# SCH_ardiuno_2024-06-28.net
KiCad netlist of a schematic drawn in EasyEDA
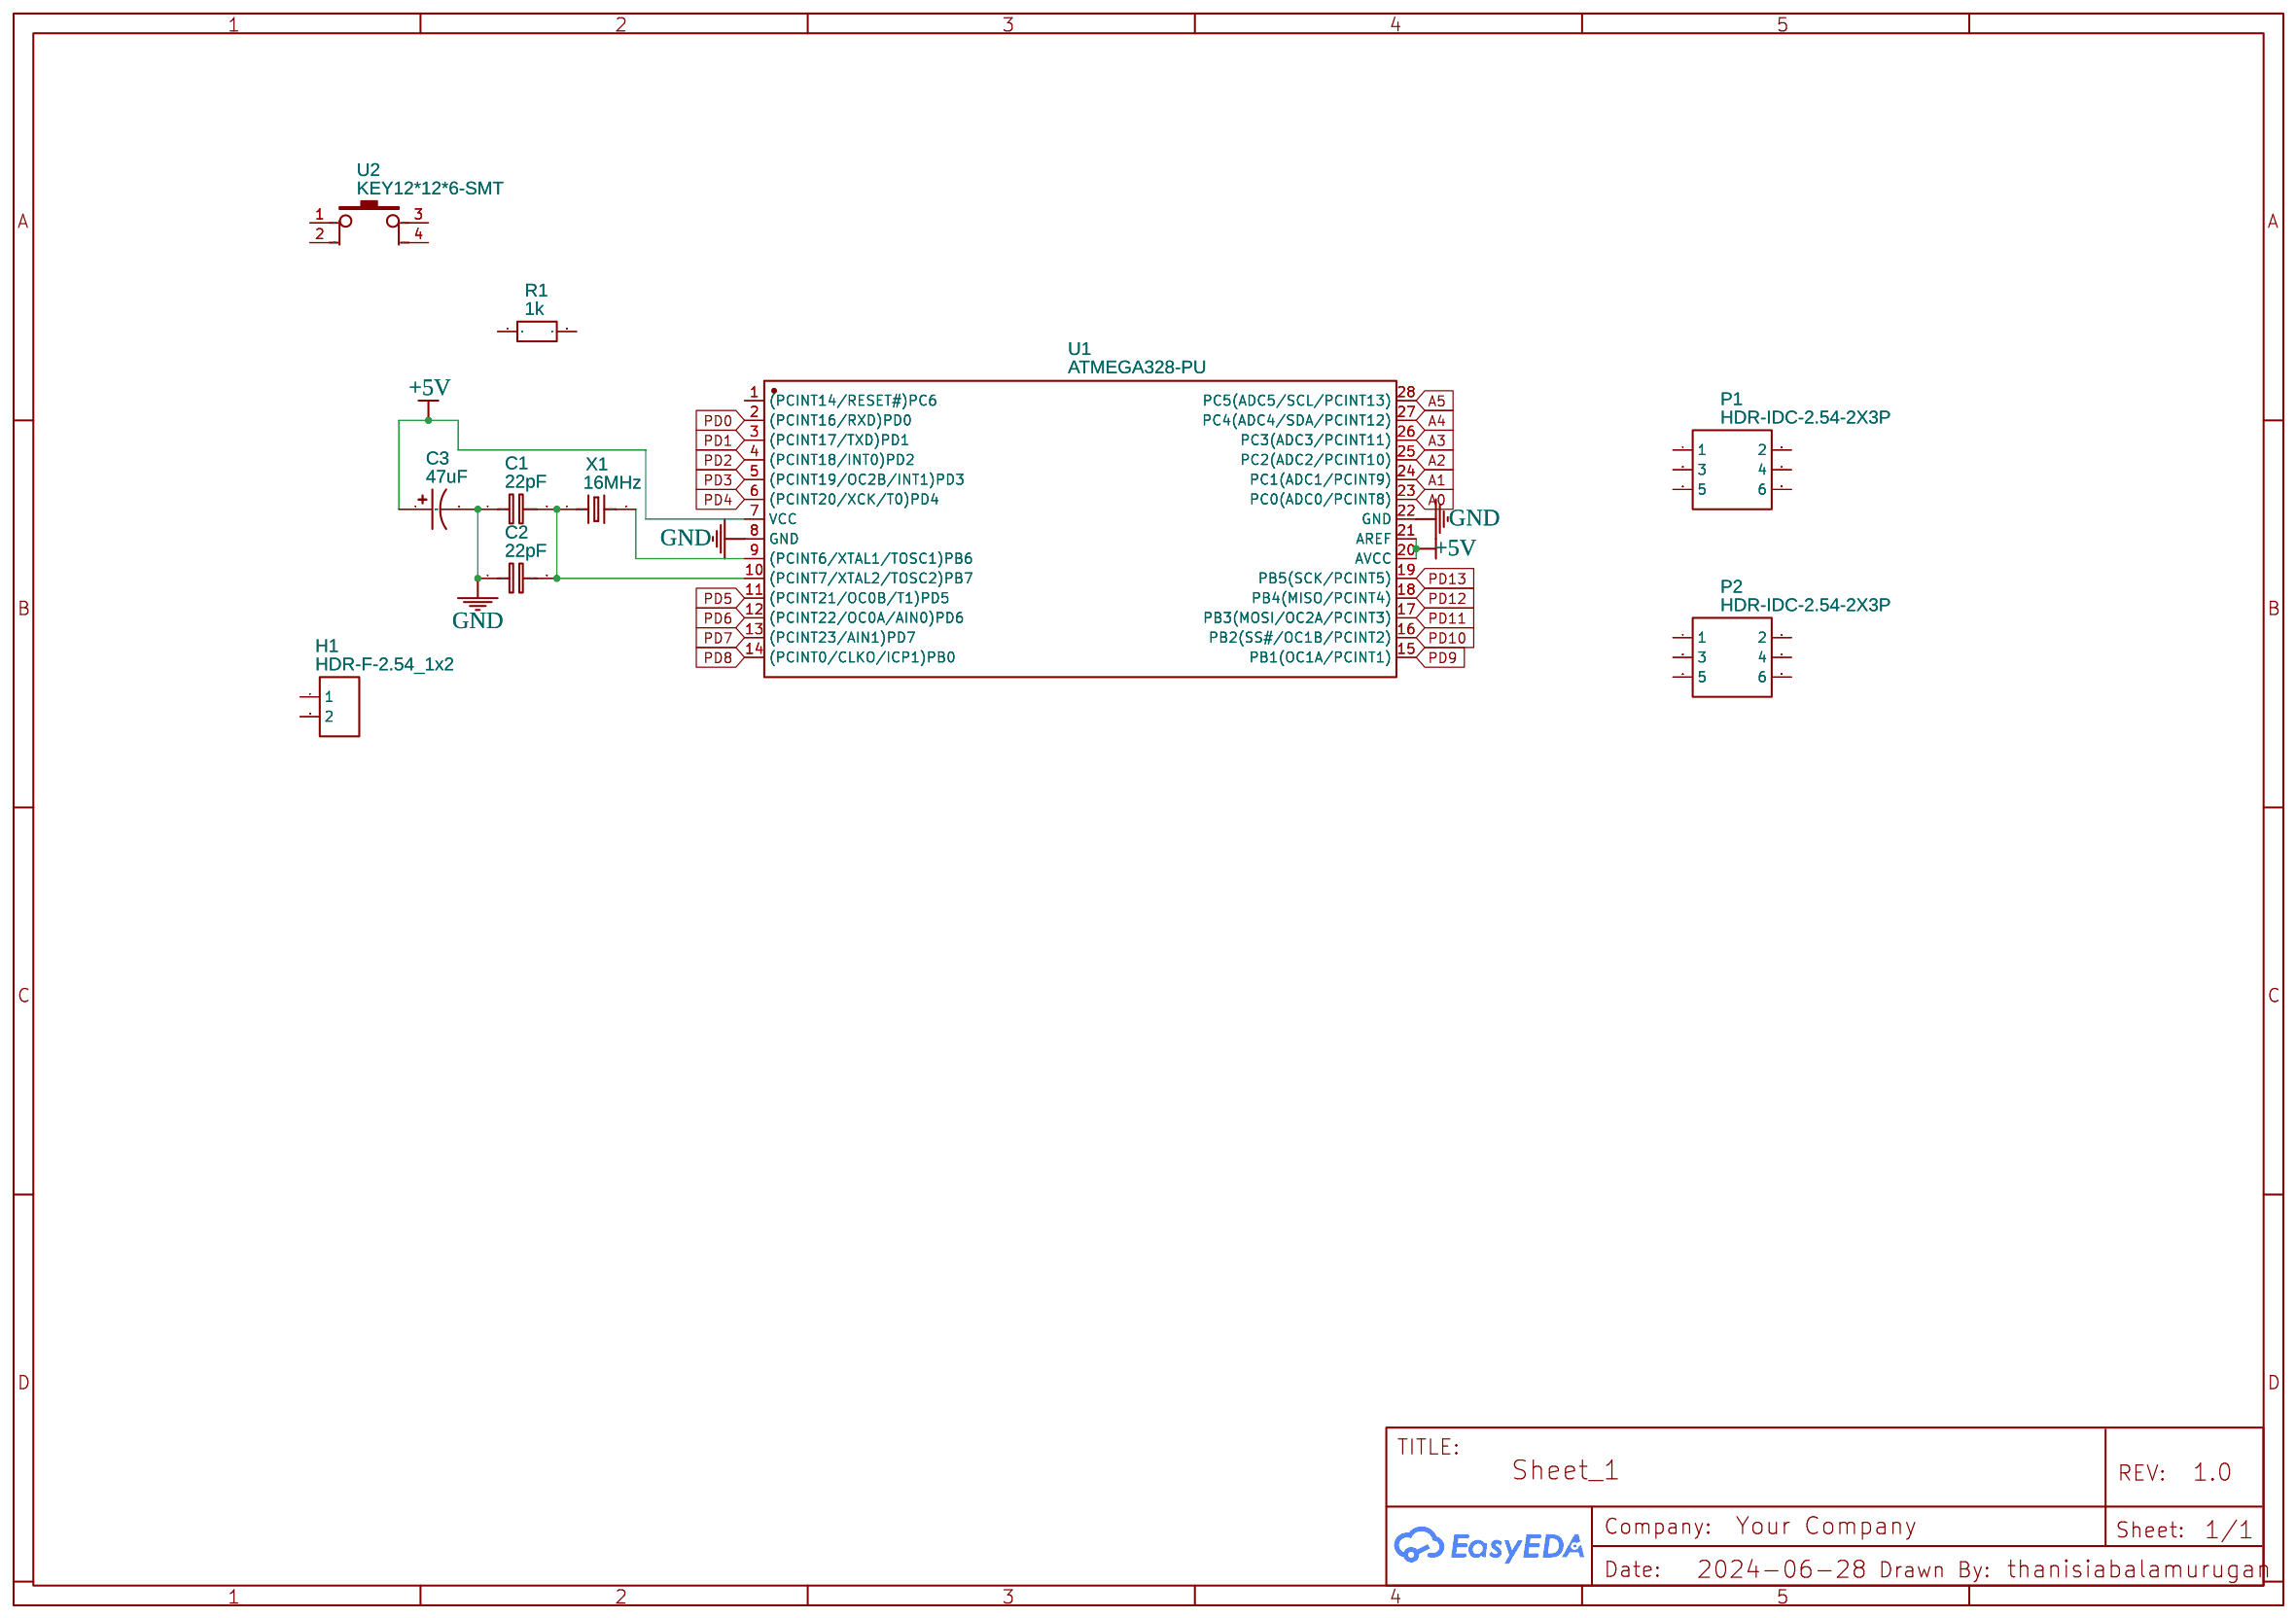
[diagram p0: schematic sheet]

(export (version "E")
  (design (tool "Eeschema 10.0.6"))
  (components
    (comp (ref "C1") (value "22pF") (libsource (lib "") (part "C_0603_EU")))
    (comp (ref "C2") (value "22pF") (libsource (lib "") (part "C_0603_EU")))
    (comp (ref "C3") (value "47uF") (libsource (lib "") (part "C_Tan_SMD_A_US")))
    (comp (ref "H1") (value "HDR-F-2.54_1x2") (libsource (lib "") (part "HDR-F-2.54_1x2")))
    (comp (ref "P1")
      (value "HDR-IDC-2.54-2X3P")
      (fields (field (name "Manufacturer Part") "2X3 2.54mm IDC Box") (field (name "Manufacturer") "BOOMELE"))
      (libsource (lib "") (part "HDR-IDC-2.54-2X3P"))
    )
    (comp (ref "P2")
      (value "HDR-IDC-2.54-2X3P")
      (fields (field (name "Manufacturer Part") "2X3 2.54mm IDC Box") (field (name "Manufacturer") "BOOMELE"))
      (libsource (lib "") (part "HDR-IDC-2.54-2X3P"))
    )
    (comp (ref "R1") (value "1k") (libsource (lib "") (part "R_0603_EU")))
    (comp (ref "U1")
      (value "ATMEGA328-PU")
      (fields (field (name "Manufacturer") "MICROCHIP(美国微芯)"))
      (libsource (lib "") (part "ATMEGA328-PU"))
    )
    (comp (ref "U2") (value "KEY12*12*6-SMT") (libsource (lib "") (part "KEY12*12*6-SMT")))
    (comp (ref "X1")
      (value "16MHz")
      (fields
        (field (name "Manufacturer Part") "XIHCELNANF-16MHZ")
        (field (name "Manufacturer") "TAITIEN(泰艺电子)")
      )
      (libsource (lib "") (part "XIHCELNANF-16MHZ"))
    )
  )
  (nets
    (net (code "1") (name "+5V") (class "Default")
      (node (ref "C3") (pin "1") (pinfunction "1_1") (pintype "unspecified"))
      (node (ref "U1") (pin "20") (pinfunction "AVCC_20") (pintype "unspecified"))
      (node (ref "U1") (pin "21") (pinfunction "AREF_21") (pintype "unspecified"))
      (node (ref "U1") (pin "7") (pinfunction "VCC_7") (pintype "unspecified"))
    )
    (net (code "2") (name "A0") (class "Default")
      (node (ref "U1") (pin "23") (pinfunction "PC0(ADC0/PCINT8)_23") (pintype "unspecified"))
    )
    (net (code "3") (name "A1") (class "Default")
      (node (ref "U1") (pin "24") (pinfunction "PC1(ADC1/PCINT9)_24") (pintype "unspecified"))
    )
    (net (code "4") (name "A2") (class "Default")
      (node (ref "U1") (pin "25") (pinfunction "PC2(ADC2/PCINT10)_25") (pintype "unspecified"))
    )
    (net (code "5") (name "A3") (class "Default")
      (node (ref "U1") (pin "26") (pinfunction "PC3(ADC3/PCINT11)_26") (pintype "unspecified"))
    )
    (net (code "6") (name "A4") (class "Default")
      (node (ref "U1") (pin "27") (pinfunction "PC4(ADC4/SDA/PCINT12)_27") (pintype "unspecified"))
    )
    (net (code "7") (name "A5") (class "Default")
      (node (ref "U1") (pin "28") (pinfunction "PC5(ADC5/SCL/PCINT13)_28") (pintype "unspecified"))
    )
    (net (code "8") (name "GND") (class "Default")
      (node (ref "C1") (pin "1") (pinfunction "1_1") (pintype "unspecified"))
      (node (ref "C2") (pin "1") (pinfunction "1_1") (pintype "unspecified"))
      (node (ref "C3") (pin "2") (pinfunction "2_2") (pintype "unspecified"))
      (node (ref "U1") (pin "22") (pinfunction "GND_22") (pintype "unspecified"))
      (node (ref "U1") (pin "8") (pinfunction "GND_8") (pintype "unspecified"))
    )
    (net (code "9") (name "Net-(U1-(PCINT6{slash}XTAL1{slash}TOSC1)PB6)") (class "Default")
      (node (ref "U1") (pin "9") (pinfunction "(PCINT6/XTAL1/TOSC1)PB6_9") (pintype "unspecified"))
      (node (ref "X1") (pin "2") (pinfunction "2_2") (pintype "unspecified"))
    )
    (net (code "10") (name "Net-(U1-(PCINT7{slash}XTAL2{slash}TOSC2)PB7)") (class "Default")
      (node (ref "C1") (pin "2") (pinfunction "2_2") (pintype "unspecified"))
      (node (ref "C2") (pin "2") (pinfunction "2_2") (pintype "unspecified"))
      (node (ref "U1") (pin "10") (pinfunction "(PCINT7/XTAL2/TOSC2)PB7_10") (pintype "unspecified"))
      (node (ref "X1") (pin "1") (pinfunction "1_1") (pintype "unspecified"))
    )
    (net (code "11") (name "PD0") (class "Default")
      (node (ref "U1") (pin "2") (pinfunction "(PCINT16/RXD)PD0_2") (pintype "unspecified"))
    )
    (net (code "12") (name "PD1") (class "Default")
      (node (ref "U1") (pin "3") (pinfunction "(PCINT17/TXD)PD1_3") (pintype "unspecified"))
    )
    (net (code "13") (name "PD2") (class "Default")
      (node (ref "U1") (pin "4") (pinfunction "(PCINT18/INT0)PD2_4") (pintype "unspecified"))
    )
    (net (code "14") (name "PD3") (class "Default")
      (node (ref "U1") (pin "5") (pinfunction "(PCINT19/OC2B/INT1)PD3_5") (pintype "unspecified"))
    )
    (net (code "15") (name "PD4") (class "Default")
      (node (ref "U1") (pin "6") (pinfunction "(PCINT20/XCK/T0)PD4_6") (pintype "unspecified"))
    )
    (net (code "16") (name "PD5") (class "Default")
      (node (ref "U1") (pin "11") (pinfunction "(PCINT21/OC0B/T1)PD5_11") (pintype "unspecified"))
    )
    (net (code "17") (name "PD6") (class "Default")
      (node (ref "U1") (pin "12") (pinfunction "(PCINT22/OC0A/AIN0)PD6_12") (pintype "unspecified"))
    )
    (net (code "18") (name "PD7") (class "Default")
      (node (ref "U1") (pin "13") (pinfunction "(PCINT23/AIN1)PD7_13") (pintype "unspecified"))
    )
    (net (code "19") (name "PD8") (class "Default")
      (node (ref "U1") (pin "14") (pinfunction "(PCINT0/CLKO/ICP1)PB0_14") (pintype "unspecified"))
    )
    (net (code "20") (name "PD9") (class "Default")
      (node (ref "U1") (pin "15") (pinfunction "PB1(OC1A/PCINT1)_15") (pintype "unspecified"))
    )
    (net (code "21") (name "PD10") (class "Default")
      (node (ref "U1") (pin "16") (pinfunction "PB2(SS#/OC1B/PCINT2)_16") (pintype "unspecified"))
    )
    (net (code "22") (name "PD11") (class "Default")
      (node (ref "U1") (pin "17") (pinfunction "PB3(MOSI/OC2A/PCINT3)_17") (pintype "unspecified"))
    )
    (net (code "23") (name "PD12") (class "Default")
      (node (ref "U1") (pin "18") (pinfunction "PB4(MISO/PCINT4)_18") (pintype "unspecified"))
    )
    (net (code "24") (name "PD13") (class "Default")
      (node (ref "U1") (pin "19") (pinfunction "PB5(SCK/PCINT5)_19") (pintype "unspecified"))
    )
    (net (code "25") (name "unconnected-(H1-Pad1)") (class "Default")
      (node (ref "H1") (pin "1") (pinfunction "1_1") (pintype "input"))
    )
    (net (code "26") (name "unconnected-(H1-Pad2)") (class "Default")
      (node (ref "H1") (pin "2") (pinfunction "2_2") (pintype "input"))
    )
    (net (code "27") (name "unconnected-(P1-Pad1)") (class "Default")
      (node (ref "P1") (pin "1") (pinfunction "1_1") (pintype "unspecified"))
    )
    (net (code "28") (name "unconnected-(P1-Pad2)") (class "Default")
      (node (ref "P1") (pin "2") (pinfunction "2_2") (pintype "unspecified"))
    )
    (net (code "29") (name "unconnected-(P1-Pad3)") (class "Default")
      (node (ref "P1") (pin "3") (pinfunction "3_3") (pintype "unspecified"))
    )
    (net (code "30") (name "unconnected-(P1-Pad4)") (class "Default")
      (node (ref "P1") (pin "4") (pinfunction "4_4") (pintype "unspecified"))
    )
    (net (code "31") (name "unconnected-(P1-Pad5)") (class "Default")
      (node (ref "P1") (pin "5") (pinfunction "5_5") (pintype "unspecified"))
    )
    (net (code "32") (name "unconnected-(P1-Pad6)") (class "Default")
      (node (ref "P1") (pin "6") (pinfunction "6_6") (pintype "unspecified"))
    )
    (net (code "33") (name "unconnected-(P2-Pad1)") (class "Default")
      (node (ref "P2") (pin "1") (pinfunction "1_1") (pintype "unspecified"))
    )
    (net (code "34") (name "unconnected-(P2-Pad2)") (class "Default")
      (node (ref "P2") (pin "2") (pinfunction "2_2") (pintype "unspecified"))
    )
    (net (code "35") (name "unconnected-(P2-Pad3)") (class "Default")
      (node (ref "P2") (pin "3") (pinfunction "3_3") (pintype "unspecified"))
    )
    (net (code "36") (name "unconnected-(P2-Pad4)") (class "Default")
      (node (ref "P2") (pin "4") (pinfunction "4_4") (pintype "unspecified"))
    )
    (net (code "37") (name "unconnected-(P2-Pad5)") (class "Default")
      (node (ref "P2") (pin "5") (pinfunction "5_5") (pintype "unspecified"))
    )
    (net (code "38") (name "unconnected-(P2-Pad6)") (class "Default")
      (node (ref "P2") (pin "6") (pinfunction "6_6") (pintype "unspecified"))
    )
    (net (code "39") (name "unconnected-(R1-Pad1)") (class "Default")
      (node (ref "R1") (pin "1") (pinfunction "1_1") (pintype "unspecified"))
    )
    (net (code "40") (name "unconnected-(R1-Pad2)") (class "Default")
      (node (ref "R1") (pin "2") (pinfunction "2_2") (pintype "unspecified"))
    )
    (net (code "41") (name "unconnected-(U1-(PCINT14{slash}RESET#)PC6-Pad1)") (class "Default")
      (node (ref "U1") (pin "1") (pinfunction "(PCINT14/RESET#)PC6_1") (pintype "unspecified"))
    )
    (net (code "42") (name "unconnected-(U2-Pad1)") (class "Default")
      (node (ref "U2") (pin "1") (pinfunction "1_1") (pintype "input"))
    )
    (net (code "43") (name "unconnected-(U2-Pad2)") (class "Default")
      (node (ref "U2") (pin "2") (pinfunction "2_2") (pintype "input"))
    )
    (net (code "44") (name "unconnected-(U2-Pad3)") (class "Default")
      (node (ref "U2") (pin "3") (pinfunction "3_3") (pintype "input"))
    )
    (net (code "45") (name "unconnected-(U2-Pad4)") (class "Default")
      (node (ref "U2") (pin "4") (pinfunction "4_4") (pintype "input"))
    )
  )
)
